# stlink-v3-hwmod.net
KiCad netlist of a schematic drawn in EAGLE
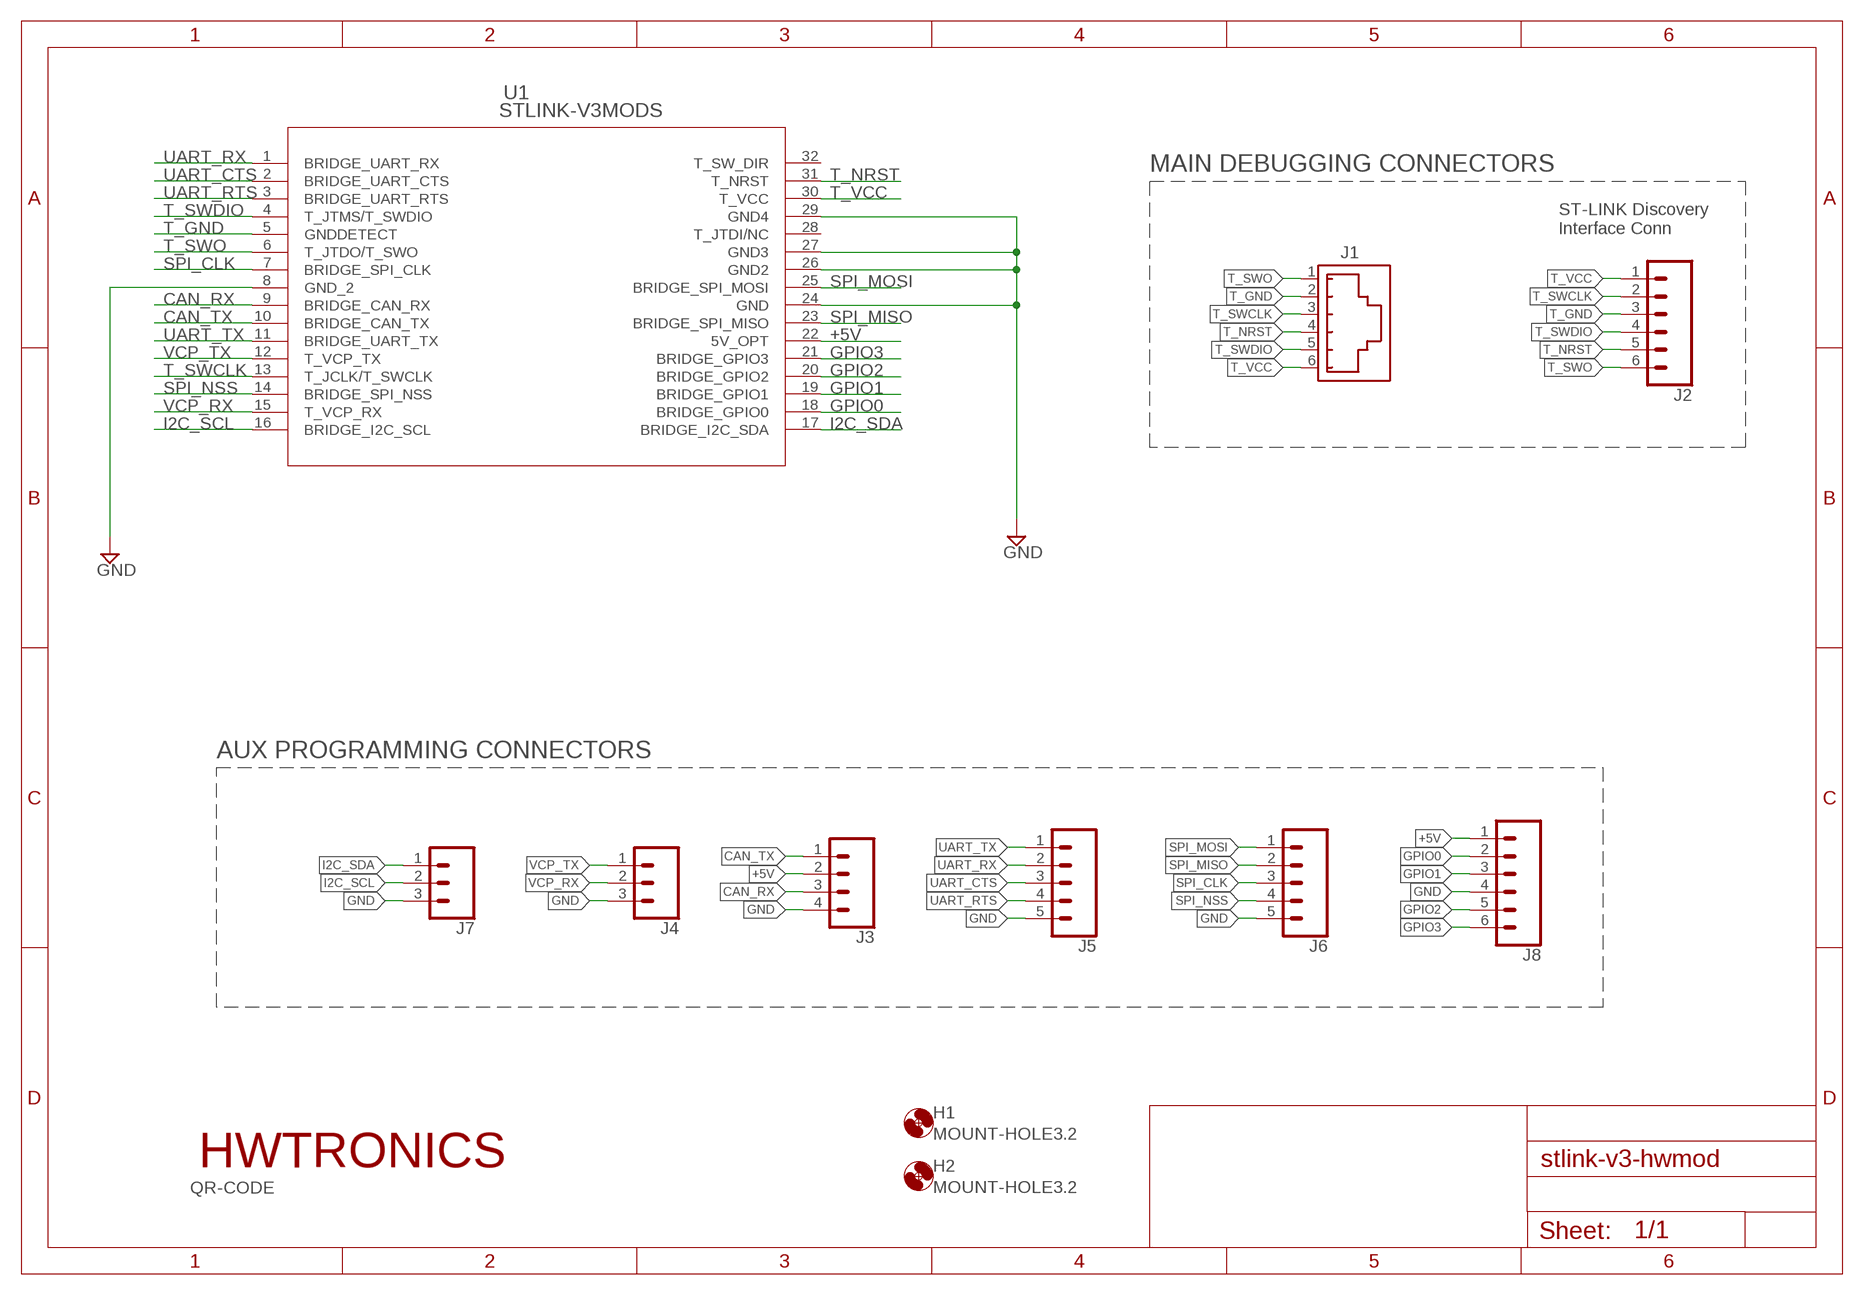
[diagram p0: schematic, sheet 1]

(export (version "E")
  (design (tool "Eeschema 10.0.6"))
  (components
    (comp (ref "H1")
      (value "MOUNT-HOLE3.2")
      (footprint "eagle-import:3,2")
      (libsource (lib "eagle-import") (part "MOUNT-HOLE3.2"))
    )
    (comp (ref "H2")
      (value "MOUNT-HOLE3.2")
      (footprint "eagle-import:3,2")
      (libsource (lib "eagle-import") (part "MOUNT-HOLE3.2"))
    )
    (comp (ref "J1")
      (value "615006143621")
      (footprint "eagle-import:615006143621")
      (libsource (lib "eagle-import") (part "615006143621"))
    )
    (comp (ref "J2")
      (value "CONN_06SILK_FEMALE_PTH")
      (footprint "eagle-import:1X06")
      (libsource (lib "eagle-import") (part "CONN_06SILK_FEMALE_PTH"))
    )
    (comp (ref "J3")
      (value "CONN_04")
      (footprint "eagle-import:1X04")
      (libsource (lib "eagle-import") (part "CONN_04"))
    )
    (comp (ref "J4")
      (value "CONN_03")
      (footprint "eagle-import:1X03")
      (libsource (lib "eagle-import") (part "CONN_03"))
    )
    (comp (ref "J5")
      (value "CONN_05")
      (footprint "eagle-import:1X05")
      (libsource (lib "eagle-import") (part "CONN_05"))
    )
    (comp (ref "J6")
      (value "CONN_05")
      (footprint "eagle-import:1X05")
      (libsource (lib "eagle-import") (part "CONN_05"))
    )
    (comp (ref "J7")
      (value "CONN_03")
      (footprint "eagle-import:1X03")
      (libsource (lib "eagle-import") (part "CONN_03"))
    )
    (comp (ref "J8")
      (value "CONN_06SILK_FEMALE_PTH")
      (footprint "eagle-import:1X06")
      (libsource (lib "eagle-import") (part "CONN_06SILK_FEMALE_PTH"))
    )
    (comp (ref "LOGO1")
      (value "LOGO-HWTRONICS-10MM")
      (footprint "eagle-import:HWTRONICS-10MM")
      (libsource (lib "eagle-import") (part "LOGO-HWTRONICS-10MM"))
    )
    (comp (ref "U$1")
      (value "STLINK-V3-HWMODS")
      (footprint "eagle-import:STLINK-V3-HWMODS")
      (libsource (lib "eagle-import") (part "STLINK-V3-HWMODS"))
    )
    (comp (ref "U1")
      (value "STLINK-V3MODS")
      (footprint "eagle-import:MOD_STLINK-V3M_MB1467")
      (fields (field (name "MANUFACTURER_PART_NUMBER") "STLINKV3MOS"))
      (libsource (lib "eagle-import") (part "STLINK-V3MODS"))
    )
  )
  (nets
    (net (code "1") (name "+5V") (class "Default")
      (node (ref "J3") (pin "2") (pinfunction "2_2") (pintype "passive"))
      (node (ref "J8") (pin "1") (pinfunction "1_1") (pintype "passive"))
      (node (ref "U1") (pin "22") (pinfunction "5V_OPT_22") (pintype "passive"))
    )
    (net (code "2") (name "CAN_RX") (class "Default")
      (node (ref "J3") (pin "3") (pinfunction "3_3") (pintype "passive"))
      (node (ref "U1") (pin "9") (pinfunction "BRIDGE_CAN_RX_9") (pintype "passive"))
    )
    (net (code "3") (name "CAN_TX") (class "Default")
      (node (ref "J3") (pin "1") (pinfunction "1_1") (pintype "passive"))
      (node (ref "U1") (pin "10") (pinfunction "BRIDGE_CAN_TX_10") (pintype "passive"))
    )
    (net (code "4") (name "GND") (class "Default")
      (node (ref "J3") (pin "4") (pinfunction "4_4") (pintype "passive"))
      (node (ref "J4") (pin "3") (pinfunction "3_3") (pintype "passive"))
      (node (ref "J5") (pin "5") (pinfunction "5_5") (pintype "passive"))
      (node (ref "J6") (pin "5") (pinfunction "5_5") (pintype "passive"))
      (node (ref "J7") (pin "3") (pinfunction "3_3") (pintype "passive"))
      (node (ref "J8") (pin "4") (pinfunction "4_4") (pintype "passive"))
      (node (ref "U1") (pin "24") (pinfunction "GND_24") (pintype "passive"))
      (node (ref "U1") (pin "26") (pinfunction "GND2_26") (pintype "passive"))
      (node (ref "U1") (pin "27") (pinfunction "GND3_27") (pintype "passive"))
      (node (ref "U1") (pin "29") (pinfunction "GND4_29") (pintype "passive"))
      (node (ref "U1") (pin "8") (pinfunction "GND_2_8") (pintype "passive"))
    )
    (net (code "5") (name "GPIO0") (class "Default")
      (node (ref "J8") (pin "2") (pinfunction "2_2") (pintype "passive"))
      (node (ref "U1") (pin "18") (pinfunction "BRIDGE_GPIO0_18") (pintype "bidirectional"))
    )
    (net (code "6") (name "GPIO1") (class "Default")
      (node (ref "J8") (pin "3") (pinfunction "3_3") (pintype "passive"))
      (node (ref "U1") (pin "19") (pinfunction "BRIDGE_GPIO1_19") (pintype "bidirectional"))
    )
    (net (code "7") (name "GPIO2") (class "Default")
      (node (ref "J8") (pin "5") (pinfunction "5_5") (pintype "passive"))
      (node (ref "U1") (pin "20") (pinfunction "BRIDGE_GPIO2_20") (pintype "bidirectional"))
    )
    (net (code "8") (name "GPIO3") (class "Default")
      (node (ref "J8") (pin "6") (pinfunction "6_6") (pintype "passive"))
      (node (ref "U1") (pin "21") (pinfunction "BRIDGE_GPIO3_21") (pintype "bidirectional"))
    )
    (net (code "9") (name "I2C_SCL") (class "Default")
      (node (ref "J7") (pin "2") (pinfunction "2_2") (pintype "passive"))
      (node (ref "U1") (pin "16") (pinfunction "BRIDGE_I2C_SCL_16") (pintype "bidirectional"))
    )
    (net (code "10") (name "I2C_SDA") (class "Default")
      (node (ref "J7") (pin "1") (pinfunction "1_1") (pintype "passive"))
      (node (ref "U1") (pin "17") (pinfunction "BRIDGE_I2C_SDA_17") (pintype "bidirectional"))
    )
    (net (code "11") (name "SPI_CLK") (class "Default")
      (node (ref "J6") (pin "3") (pinfunction "3_3") (pintype "passive"))
      (node (ref "U1") (pin "7") (pinfunction "BRIDGE_SPI_CLK_7") (pintype "passive"))
    )
    (net (code "12") (name "SPI_MISO") (class "Default")
      (node (ref "J6") (pin "2") (pinfunction "2_2") (pintype "passive"))
      (node (ref "U1") (pin "23") (pinfunction "BRIDGE_SPI_MISO_23") (pintype "passive"))
    )
    (net (code "13") (name "SPI_MOSI") (class "Default")
      (node (ref "J6") (pin "1") (pinfunction "1_1") (pintype "passive"))
      (node (ref "U1") (pin "25") (pinfunction "BRIDGE_SPI_MOSI_25") (pintype "passive"))
    )
    (net (code "14") (name "SPI_NSS") (class "Default")
      (node (ref "J6") (pin "4") (pinfunction "4_4") (pintype "passive"))
      (node (ref "U1") (pin "14") (pinfunction "BRIDGE_SPI_NSS_14") (pintype "passive"))
    )
    (net (code "15") (name "T_GND") (class "Default")
      (node (ref "J1") (pin "2") (pinfunction "5_2") (pintype "passive"))
      (node (ref "J2") (pin "3") (pinfunction "3_3") (pintype "passive"))
      (node (ref "U1") (pin "5") (pinfunction "GNDDETECT_5") (pintype "passive"))
    )
    (net (code "16") (name "T_NRST") (class "Default")
      (node (ref "J1") (pin "4") (pinfunction "3_4") (pintype "passive"))
      (node (ref "J2") (pin "5") (pinfunction "5_5") (pintype "passive"))
      (node (ref "U1") (pin "31") (pinfunction "T_NRST_31") (pintype "passive"))
    )
    (net (code "17") (name "T_SWCLK") (class "Default")
      (node (ref "J1") (pin "3") (pinfunction "4_3") (pintype "passive"))
      (node (ref "J2") (pin "2") (pinfunction "2_2") (pintype "passive"))
      (node (ref "U1") (pin "13") (pinfunction "T_JCLK/T_SWCLK_13") (pintype "passive"))
    )
    (net (code "18") (name "T_SWDIO") (class "Default")
      (node (ref "J1") (pin "5") (pinfunction "2_5") (pintype "passive"))
      (node (ref "J2") (pin "4") (pinfunction "4_4") (pintype "passive"))
      (node (ref "U1") (pin "4") (pinfunction "T_JTMS/T_SWDIO_4") (pintype "passive"))
    )
    (net (code "19") (name "T_SWO") (class "Default")
      (node (ref "J1") (pin "1") (pinfunction "6_1") (pintype "passive"))
      (node (ref "J2") (pin "6") (pinfunction "6_6") (pintype "passive"))
      (node (ref "U1") (pin "6") (pinfunction "T_JTDO/T_SWO_6") (pintype "passive"))
    )
    (net (code "20") (name "T_VCC") (class "Default")
      (node (ref "J1") (pin "6") (pinfunction "1_6") (pintype "passive"))
      (node (ref "J2") (pin "1") (pinfunction "1_1") (pintype "passive"))
      (node (ref "U1") (pin "30") (pinfunction "T_VCC_30") (pintype "passive"))
    )
    (net (code "21") (name "UART_CTS") (class "Default")
      (node (ref "J5") (pin "3") (pinfunction "3_3") (pintype "passive"))
      (node (ref "U1") (pin "2") (pinfunction "BRIDGE_UART_CTS_2") (pintype "passive"))
    )
    (net (code "22") (name "UART_RTS") (class "Default")
      (node (ref "J5") (pin "4") (pinfunction "4_4") (pintype "passive"))
      (node (ref "U1") (pin "3") (pinfunction "BRIDGE_UART_RTS_3") (pintype "passive"))
    )
    (net (code "23") (name "UART_RX") (class "Default")
      (node (ref "J5") (pin "2") (pinfunction "2_2") (pintype "passive"))
      (node (ref "U1") (pin "1") (pinfunction "BRIDGE_UART_RX_1") (pintype "passive"))
    )
    (net (code "24") (name "UART_TX") (class "Default")
      (node (ref "J5") (pin "1") (pinfunction "1_1") (pintype "passive"))
      (node (ref "U1") (pin "11") (pinfunction "BRIDGE_UART_TX_11") (pintype "passive"))
    )
    (net (code "25") (name "VCP_RX") (class "Default")
      (node (ref "J4") (pin "2") (pinfunction "2_2") (pintype "passive"))
      (node (ref "U1") (pin "15") (pinfunction "T_VCP_RX_15") (pintype "passive"))
    )
    (net (code "26") (name "VCP_TX") (class "Default")
      (node (ref "J4") (pin "1") (pinfunction "1_1") (pintype "passive"))
      (node (ref "U1") (pin "12") (pinfunction "T_VCP_TX_12") (pintype "passive"))
    )
    (net (code "27") (name "unconnected-(U1-T_JTDI{slash}NC-Pad28)") (class "Default")
      (node (ref "U1") (pin "28") (pinfunction "T_JTDI/NC_28") (pintype "passive"))
    )
    (net (code "28") (name "unconnected-(U1-T_SW_DIR-Pad32)") (class "Default")
      (node (ref "U1") (pin "32") (pinfunction "T_SW_DIR_32") (pintype "passive"))
    )
  )
)
